# Agena.net
KiCad netlist of a schematic drawn in EAGLE
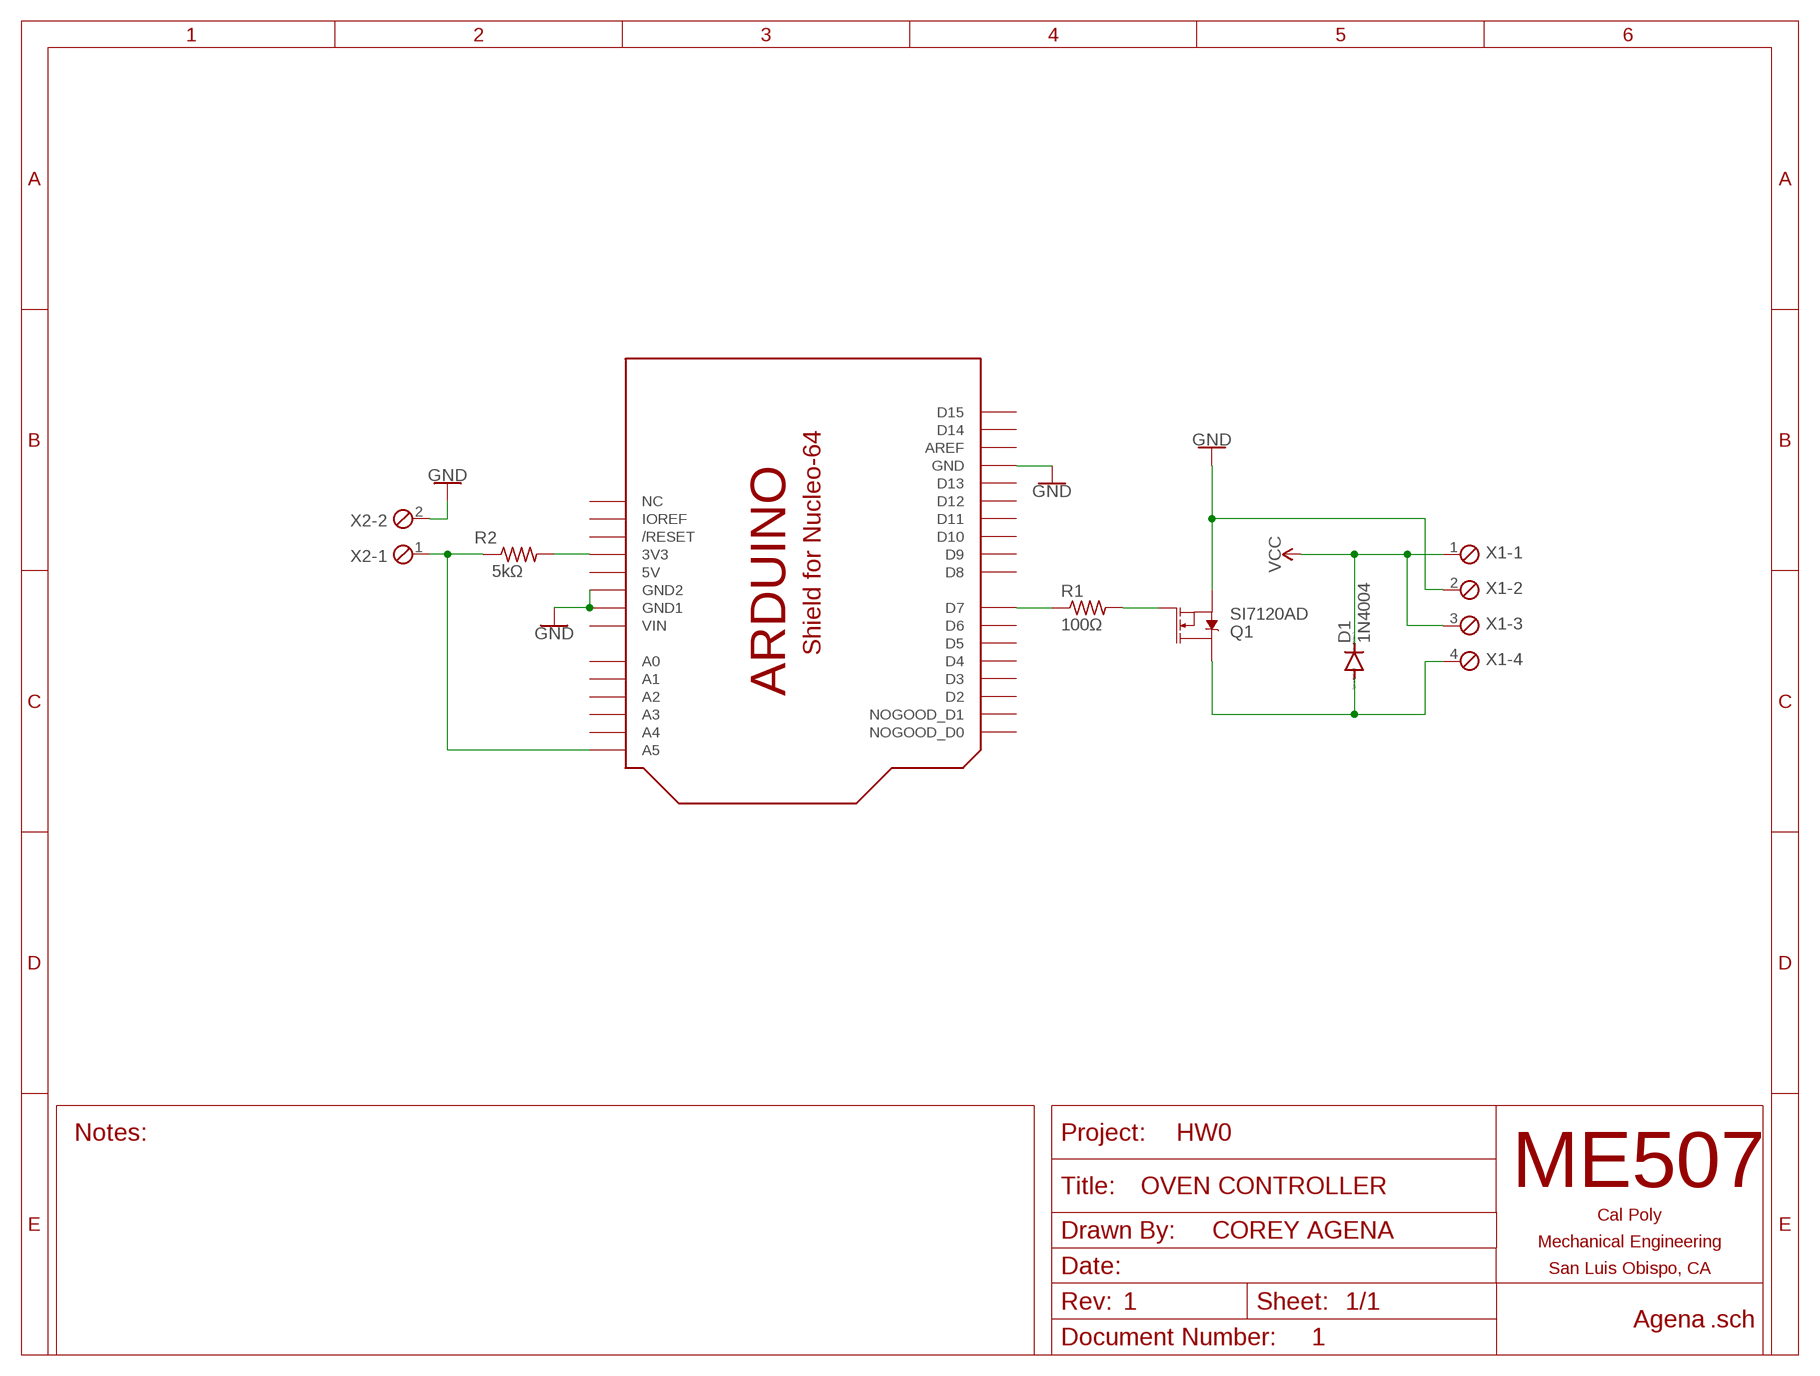
[diagram p0: schematic, sheet 1]

(export (version "E")
  (design (tool "Eeschema 10.0.6"))
  (components
    (comp (ref "D1")
      (value "1N4004")
      (footprint "eagle-import:DO41-10")
      (libsource (lib "eagle-import") (part "1N4004"))
    )
    (comp (ref "Q1")
      (value "SI7120AD")
      (footprint "eagle-import:1212-8")
      (libsource (lib "eagle-import") (part "SI7120AD"))
    )
    (comp (ref "R1")
      (value "100Ω")
      (footprint "eagle-import:R0805")
      (libsource (lib "eagle-import") (part "R-US_R0805"))
    )
    (comp (ref "R2")
      (value "5kΩ")
      (footprint "eagle-import:M0805")
      (libsource (lib "eagle-import") (part "R-US_M0805"))
    )
    (comp (ref "U$1")
      (value "SHIELD_FOR_NUCLE0_64_SHORT")
      (footprint "eagle-import:SHIELD_FOR_NUCLEO_64_SHORT")
      (libsource (lib "eagle-import") (part "SHIELD_FOR_NUCLE0_64_SHORT"))
    )
    (comp (ref "X1")
      (value "SCREWTERM_4P_381")
      (footprint "eagle-import:4POL381")
      (libsource (lib "eagle-import") (part "SCREWTERM_4P_381"))
    )
    (comp (ref "X2")
      (value "SCREWTERM_2P_254")
      (footprint "eagle-import:2POL254")
      (libsource (lib "eagle-import") (part "SCREWTERM_2P_254"))
    )
  )
  (nets
    (net (code "1") (name "/5V") (class "Default")
      (node (ref "U$1") (pin "5V") (pinfunction "5V_5V") (pintype "power_in"))
    )
    (net (code "2") (name "/VIN") (class "Default")
      (node (ref "U$1") (pin "VIN") (pinfunction "VIN_VIN") (pintype "power_in"))
    )
    (net (code "3") (name "GND") (class "Default")
      (node (ref "Q1") (pin "1") (pinfunction "S_1") (pintype "bidirectional"))
      (node (ref "Q1") (pin "2") (pinfunction "S_2") (pintype "bidirectional"))
      (node (ref "Q1") (pin "3") (pinfunction "S_3") (pintype "bidirectional"))
      (node (ref "U$1") (pin "GND") (pinfunction "GND_GND") (pintype "power_in"))
      (node (ref "U$1") (pin "GND1") (pinfunction "GND1_GND1") (pintype "power_in"))
      (node (ref "U$1") (pin "GND2") (pinfunction "GND2_GND2") (pintype "power_in"))
      (node (ref "X1") (pin "2") (pinfunction "1_2") (pintype "passive"))
      (node (ref "X2") (pin "2") (pinfunction "1_2") (pintype "passive"))
    )
    (net (code "4") (name "Net-(Q1-G)") (class "Default")
      (node (ref "Q1") (pin "4") (pinfunction "G_4") (pintype "bidirectional"))
      (node (ref "R1") (pin "2") (pinfunction "2_2") (pintype "passive"))
    )
    (net (code "5") (name "Net-(R1-Pad1)") (class "Default")
      (node (ref "R1") (pin "1") (pinfunction "1_1") (pintype "passive"))
      (node (ref "U$1") (pin "D7") (pinfunction "D7_D7") (pintype "bidirectional"))
    )
    (net (code "6") (name "Net-(R2-Pad1)") (class "Default")
      (node (ref "R2") (pin "1") (pinfunction "1_1") (pintype "passive"))
      (node (ref "U$1") (pin "A5") (pinfunction "A5_A5") (pintype "bidirectional"))
      (node (ref "X2") (pin "1") (pinfunction "1_1") (pintype "passive"))
    )
    (net (code "7") (name "Net-(U$1-3V3)") (class "Default")
      (node (ref "R2") (pin "2") (pinfunction "2_2") (pintype "passive"))
      (node (ref "U$1") (pin "3V") (pinfunction "3V3_3V") (pintype "power_in"))
    )
    (net (code "8") (name "Net-(X1D-1)") (class "Default")
      (node (ref "D1") (pin "A") (pinfunction "A_A") (pintype "passive"))
      (node (ref "Q1") (pin "5") (pinfunction "D_5") (pintype "bidirectional"))
      (node (ref "Q1") (pin "6") (pinfunction "D_6") (pintype "bidirectional"))
      (node (ref "Q1") (pin "7") (pinfunction "D_7") (pintype "bidirectional"))
      (node (ref "Q1") (pin "8") (pinfunction "D_8") (pintype "bidirectional"))
      (node (ref "Q1") (pin "PAD") (pinfunction "D_PAD") (pintype "bidirectional"))
      (node (ref "X1") (pin "4") (pinfunction "1_4") (pintype "passive"))
    )
    (net (code "9") (name "VCC") (class "Default")
      (node (ref "D1") (pin "C") (pinfunction "C_C") (pintype "passive"))
      (node (ref "X1") (pin "1") (pinfunction "1_1") (pintype "passive"))
      (node (ref "X1") (pin "3") (pinfunction "1_3") (pintype "passive"))
    )
    (net (code "10") (name "unconnected-(U$1-NOGOOD_D0-PadD0)") (class "Default")
      (node (ref "U$1") (pin "D0") (pinfunction "NOGOOD_D0_D0") (pintype "no_connect"))
    )
    (net (code "11") (name "unconnected-(U$1-NOGOOD_D1-PadD1)") (class "Default")
      (node (ref "U$1") (pin "D1") (pinfunction "NOGOOD_D1_D1") (pintype "no_connect"))
    )
    (net (code "12") (name "unconnected-(U$1-PadA0)") (class "Default")
      (node (ref "U$1") (pin "A0") (pinfunction "A0_A0") (pintype "bidirectional"))
    )
    (net (code "13") (name "unconnected-(U$1-PadA1)") (class "Default")
      (node (ref "U$1") (pin "A1") (pinfunction "A1_A1") (pintype "bidirectional"))
    )
    (net (code "14") (name "unconnected-(U$1-PadA2)") (class "Default")
      (node (ref "U$1") (pin "A2") (pinfunction "A2_A2") (pintype "bidirectional"))
    )
    (net (code "15") (name "unconnected-(U$1-PadA3)") (class "Default")
      (node (ref "U$1") (pin "A3") (pinfunction "A3_A3") (pintype "bidirectional"))
    )
    (net (code "16") (name "unconnected-(U$1-PadA4)") (class "Default")
      (node (ref "U$1") (pin "A4") (pinfunction "A4_A4") (pintype "bidirectional"))
    )
    (net (code "17") (name "unconnected-(U$1-PadAREF)") (class "Default")
      (node (ref "U$1") (pin "AREF") (pinfunction "AREF_AREF") (pintype "bidirectional"))
    )
    (net (code "18") (name "unconnected-(U$1-PadD2)") (class "Default")
      (node (ref "U$1") (pin "D2") (pinfunction "D2_D2") (pintype "bidirectional"))
    )
    (net (code "19") (name "unconnected-(U$1-PadD3)") (class "Default")
      (node (ref "U$1") (pin "D3") (pinfunction "D3_D3") (pintype "bidirectional"))
    )
    (net (code "20") (name "unconnected-(U$1-PadD4)") (class "Default")
      (node (ref "U$1") (pin "D4") (pinfunction "D4_D4") (pintype "bidirectional"))
    )
    (net (code "21") (name "unconnected-(U$1-PadD5)") (class "Default")
      (node (ref "U$1") (pin "D5") (pinfunction "D5_D5") (pintype "bidirectional"))
    )
    (net (code "22") (name "unconnected-(U$1-PadD6)") (class "Default")
      (node (ref "U$1") (pin "D6") (pinfunction "D6_D6") (pintype "bidirectional"))
    )
    (net (code "23") (name "unconnected-(U$1-PadD8)") (class "Default")
      (node (ref "U$1") (pin "D8") (pinfunction "D8_D8") (pintype "bidirectional"))
    )
    (net (code "24") (name "unconnected-(U$1-PadD9)") (class "Default")
      (node (ref "U$1") (pin "D9") (pinfunction "D9_D9") (pintype "bidirectional"))
    )
    (net (code "25") (name "unconnected-(U$1-PadD10)") (class "Default")
      (node (ref "U$1") (pin "D10") (pinfunction "D10_D10") (pintype "bidirectional"))
    )
    (net (code "26") (name "unconnected-(U$1-PadD11)") (class "Default")
      (node (ref "U$1") (pin "D11") (pinfunction "D11_D11") (pintype "bidirectional"))
    )
    (net (code "27") (name "unconnected-(U$1-PadD12)") (class "Default")
      (node (ref "U$1") (pin "D12") (pinfunction "D12_D12") (pintype "bidirectional"))
    )
    (net (code "28") (name "unconnected-(U$1-PadD13)") (class "Default")
      (node (ref "U$1") (pin "D13") (pinfunction "D13_D13") (pintype "bidirectional"))
    )
    (net (code "29") (name "unconnected-(U$1-PadD14)") (class "Default")
      (node (ref "U$1") (pin "D14") (pinfunction "D14_D14") (pintype "bidirectional"))
    )
    (net (code "30") (name "unconnected-(U$1-PadD15)") (class "Default")
      (node (ref "U$1") (pin "D15") (pinfunction "D15_D15") (pintype "bidirectional"))
    )
    (net (code "31") (name "unconnected-(U$1-PadIOREF)") (class "Default")
      (node (ref "U$1") (pin "IOREF") (pinfunction "IOREF_IOREF") (pintype "bidirectional"))
    )
    (net (code "32") (name "unconnected-(U$1-PadNC)") (class "Default")
      (node (ref "U$1") (pin "NC") (pinfunction "NC_NC") (pintype "no_connect"))
    )
    (net (code "33") (name "unconnected-(U$1-{slash}RESET-PadNRST)") (class "Default")
      (node (ref "U$1") (pin "NRST") (pinfunction "/RESET_NRST") (pintype "input"))
    )
  )
)
